# RV8trimRelays.net
KiCad netlist of a schematic drawn in EAGLE
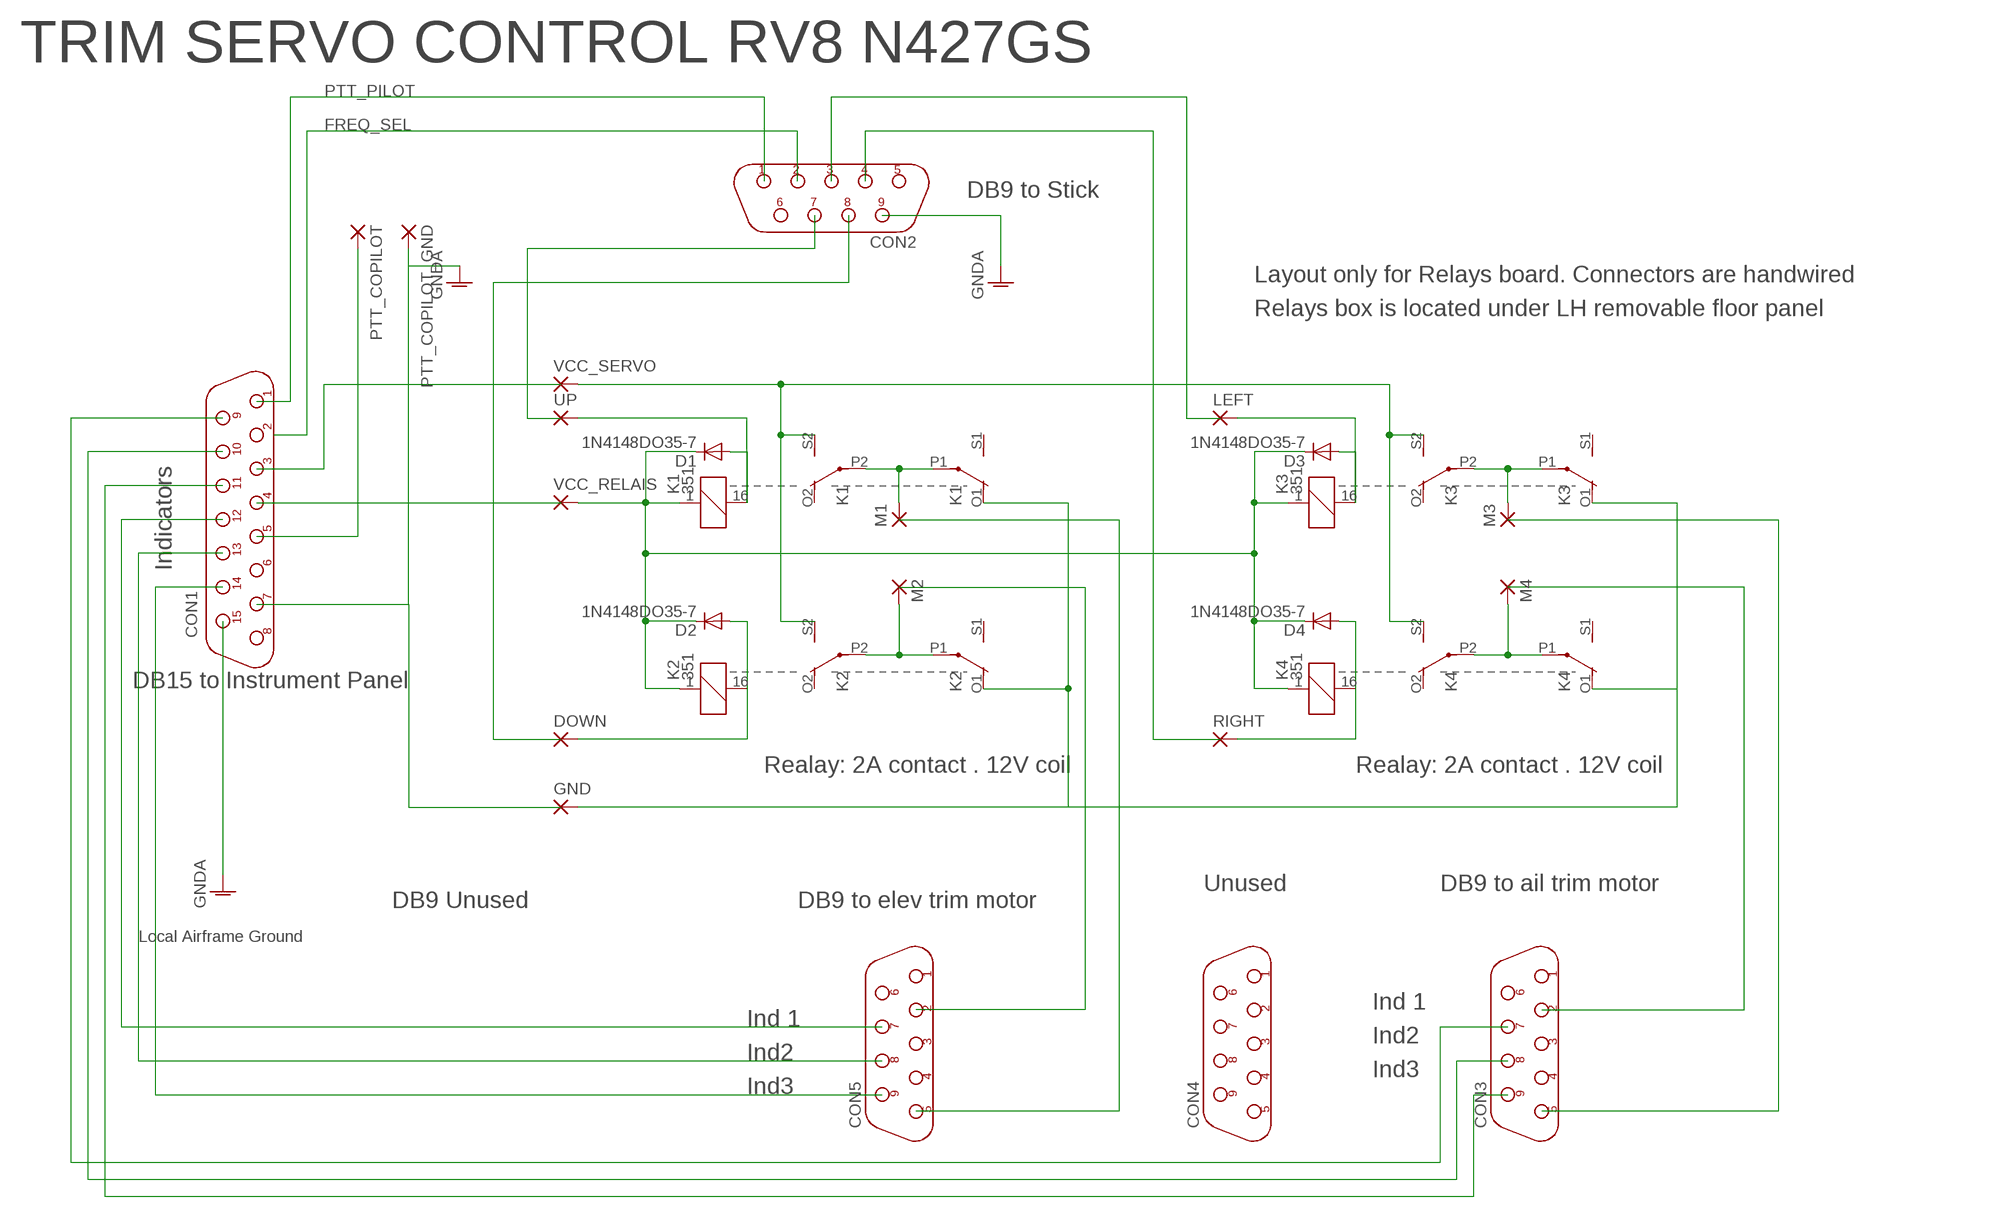
[diagram p0: schematic, sheet 1]

(export (version "E")
  (design (tool "Eeschema 10.0.6"))
  (components
    (comp (ref "CON1")
      (value "DB15F")
      (footprint "eagle-import:D-15F")
      (libsource (lib "eagle-import") (part "DB15F"))
    )
    (comp (ref "CON2")
      (value "DB9F")
      (footprint "eagle-import:D-09F")
      (libsource (lib "eagle-import") (part "DB9F"))
    )
    (comp (ref "CON3")
      (value "DB9F")
      (footprint "eagle-import:D-09F")
      (libsource (lib "eagle-import") (part "DB9F"))
    )
    (comp (ref "CON4")
      (value "DB9F")
      (footprint "eagle-import:D-09F")
      (libsource (lib "eagle-import") (part "DB9F"))
    )
    (comp (ref "CON5")
      (value "DB9F")
      (footprint "eagle-import:D-09F")
      (libsource (lib "eagle-import") (part "DB9F"))
    )
    (comp (ref "D1")
      (value "1N4148DO35-7")
      (footprint "eagle-import:DO35-7")
      (libsource (lib "eagle-import") (part "1N4148DO35-7"))
    )
    (comp (ref "D2")
      (value "1N4148DO35-7")
      (footprint "eagle-import:DO35-7")
      (libsource (lib "eagle-import") (part "1N4148DO35-7"))
    )
    (comp (ref "D3")
      (value "1N4148DO35-7")
      (footprint "eagle-import:DO35-7")
      (libsource (lib "eagle-import") (part "1N4148DO35-7"))
    )
    (comp (ref "D4")
      (value "1N4148DO35-7")
      (footprint "eagle-import:DO35-7")
      (libsource (lib "eagle-import") (part "1N4148DO35-7"))
    )
    (comp (ref "DOWN")
      (value "2,15/1,0")
      (footprint "eagle-import:2,15_1,0")
      (libsource (lib "eagle-import") (part "2,15/1,0"))
    )
    (comp (ref "GND")
      (value "2,15/1,0")
      (footprint "eagle-import:2,15_1,0")
      (libsource (lib "eagle-import") (part "2,15/1,0"))
    )
    (comp (ref "K1")
      (value "351")
      (footprint "eagle-import:351")
      (libsource (lib "eagle-import") (part "351"))
    )
    (comp (ref "K2")
      (value "351")
      (footprint "eagle-import:351")
      (libsource (lib "eagle-import") (part "351"))
    )
    (comp (ref "K3")
      (value "351")
      (footprint "eagle-import:351")
      (libsource (lib "eagle-import") (part "351"))
    )
    (comp (ref "K4")
      (value "351")
      (footprint "eagle-import:351")
      (libsource (lib "eagle-import") (part "351"))
    )
    (comp (ref "LEFT")
      (value "2,15/1,0")
      (footprint "eagle-import:2,15_1,0")
      (libsource (lib "eagle-import") (part "2,15/1,0"))
    )
    (comp (ref "M1")
      (value "2,15/1,0")
      (footprint "eagle-import:2,15_1,0")
      (libsource (lib "eagle-import") (part "2,15/1,0"))
    )
    (comp (ref "M2")
      (value "2,15/1,0")
      (footprint "eagle-import:2,15_1,0")
      (libsource (lib "eagle-import") (part "2,15/1,0"))
    )
    (comp (ref "M3")
      (value "2,15/1,0")
      (footprint "eagle-import:2,15_1,0")
      (libsource (lib "eagle-import") (part "2,15/1,0"))
    )
    (comp (ref "M4")
      (value "2,15/1,0")
      (footprint "eagle-import:2,15_1,0")
      (libsource (lib "eagle-import") (part "2,15/1,0"))
    )
    (comp (ref "PTT_COPILOT")
      (value "2,15/1,0")
      (footprint "eagle-import:2,15_1,0")
      (libsource (lib "eagle-import") (part "2,15/1,0"))
    )
    (comp (ref "PTT_COPILOT_GND")
      (value "2,15/1,0")
      (footprint "eagle-import:2,15_1,0")
      (libsource (lib "eagle-import") (part "2,15/1,0"))
    )
    (comp (ref "RIGHT")
      (value "2,15/1,0")
      (footprint "eagle-import:2,15_1,0")
      (libsource (lib "eagle-import") (part "2,15/1,0"))
    )
    (comp (ref "UP")
      (value "2,15/1,0")
      (footprint "eagle-import:2,15_1,0")
      (libsource (lib "eagle-import") (part "2,15/1,0"))
    )
    (comp (ref "VCC_RELAIS")
      (value "2,15/1,0")
      (footprint "eagle-import:2,15_1,0")
      (libsource (lib "eagle-import") (part "2,15/1,0"))
    )
    (comp (ref "VCC_SERVO")
      (value "2,15/1,0")
      (footprint "eagle-import:2,15_1,0")
      (libsource (lib "eagle-import") (part "2,15/1,0"))
    )
  )
  (nets
    (net (code "1") (name "/FREQ_SEL") (class "Default")
      (node (ref "CON2") (pin "2") (pinfunction "2_2") (pintype "passive"))
    )
    (net (code "2") (name "/PTT_PILOT") (class "Default")
      (node (ref "CON1") (pin "1") (pinfunction "1_1") (pintype "passive"))
      (node (ref "CON2") (pin "1") (pinfunction "1_1") (pintype "passive"))
    )
    (net (code "3") (name "GNDA") (class "Default")
      (node (ref "CON1") (pin "15") (pinfunction "15_15") (pintype "passive"))
      (node (ref "CON1") (pin "7") (pinfunction "7_7") (pintype "passive"))
      (node (ref "CON2") (pin "9") (pinfunction "9_9") (pintype "passive"))
      (node (ref "PTT_COPILOT_GND") (pin "1") (pinfunction "P_1") (pintype "passive"))
    )
    (net (code "4") (name "Net-(CON1-Pad9)") (class "Default")
      (node (ref "CON1") (pin "9") (pinfunction "9_9") (pintype "passive"))
      (node (ref "CON3") (pin "7") (pinfunction "7_7") (pintype "passive"))
    )
    (net (code "5") (name "Net-(CON1-Pad10)") (class "Default")
      (node (ref "CON1") (pin "10") (pinfunction "10_10") (pintype "passive"))
      (node (ref "CON3") (pin "8") (pinfunction "8_8") (pintype "passive"))
    )
    (net (code "6") (name "Net-(CON1-Pad11)") (class "Default")
      (node (ref "CON1") (pin "11") (pinfunction "11_11") (pintype "passive"))
      (node (ref "CON3") (pin "9") (pinfunction "9_9") (pintype "passive"))
    )
    (net (code "7") (name "Net-(CON1-Pad12)") (class "Default")
      (node (ref "CON1") (pin "12") (pinfunction "12_12") (pintype "passive"))
      (node (ref "CON5") (pin "7") (pinfunction "7_7") (pintype "passive"))
    )
    (net (code "8") (name "Net-(CON1-Pad13)") (class "Default")
      (node (ref "CON1") (pin "13") (pinfunction "13_13") (pintype "passive"))
      (node (ref "CON5") (pin "8") (pinfunction "8_8") (pintype "passive"))
    )
    (net (code "9") (name "Net-(CON1-Pad14)") (class "Default")
      (node (ref "CON1") (pin "14") (pinfunction "14_14") (pintype "passive"))
      (node (ref "CON5") (pin "9") (pinfunction "9_9") (pintype "passive"))
    )
    (net (code "10") (name "Net-(DOWN-P)") (class "Default")
      (node (ref "D2") (pin "A") (pinfunction "A_A") (pintype "passive"))
      (node (ref "DOWN") (pin "1") (pinfunction "P_1") (pintype "passive"))
      (node (ref "K2") (pin "16") (pinfunction "2_16") (pintype "passive"))
    )
    (net (code "11") (name "Net-(GND-P)") (class "Default")
      (node (ref "GND") (pin "1") (pinfunction "P_1") (pintype "passive"))
      (node (ref "K1") (pin "O1") (pinfunction "O_O1") (pintype "passive"))
      (node (ref "K2") (pin "O1") (pinfunction "O_O1") (pintype "passive"))
      (node (ref "K3") (pin "O1") (pinfunction "O_O1") (pintype "passive"))
      (node (ref "K4") (pin "O1") (pinfunction "O_O1") (pintype "passive"))
    )
    (net (code "12") (name "Net-(K1A-2)") (class "Default")
      (node (ref "D1") (pin "A") (pinfunction "A_A") (pintype "passive"))
      (node (ref "K1") (pin "16") (pinfunction "2_16") (pintype "passive"))
      (node (ref "UP") (pin "1") (pinfunction "P_1") (pintype "passive"))
    )
    (net (code "13") (name "Net-(K1B-P)") (class "Default")
      (node (ref "K1") (pin "P1") (pinfunction "P_P1") (pintype "passive"))
      (node (ref "K1") (pin "P2") (pinfunction "P_P2") (pintype "passive"))
      (node (ref "M1") (pin "1") (pinfunction "P_1") (pintype "passive"))
    )
    (net (code "14") (name "Net-(K1C-S)") (class "Default")
      (node (ref "K1") (pin "S2") (pinfunction "S_S2") (pintype "passive"))
      (node (ref "K2") (pin "S2") (pinfunction "S_S2") (pintype "passive"))
      (node (ref "K3") (pin "S2") (pinfunction "S_S2") (pintype "passive"))
      (node (ref "K4") (pin "S2") (pinfunction "S_S2") (pintype "passive"))
      (node (ref "VCC_SERVO") (pin "1") (pinfunction "P_1") (pintype "passive"))
    )
    (net (code "15") (name "Net-(K2B-P)") (class "Default")
      (node (ref "K2") (pin "P1") (pinfunction "P_P1") (pintype "passive"))
      (node (ref "K2") (pin "P2") (pinfunction "P_P2") (pintype "passive"))
      (node (ref "M2") (pin "1") (pinfunction "P_1") (pintype "passive"))
    )
    (net (code "16") (name "Net-(K3A-2)") (class "Default")
      (node (ref "D3") (pin "A") (pinfunction "A_A") (pintype "passive"))
      (node (ref "K3") (pin "16") (pinfunction "2_16") (pintype "passive"))
      (node (ref "LEFT") (pin "1") (pinfunction "P_1") (pintype "passive"))
    )
    (net (code "17") (name "Net-(K3B-P)") (class "Default")
      (node (ref "K3") (pin "P1") (pinfunction "P_P1") (pintype "passive"))
      (node (ref "K3") (pin "P2") (pinfunction "P_P2") (pintype "passive"))
      (node (ref "M3") (pin "1") (pinfunction "P_1") (pintype "passive"))
    )
    (net (code "18") (name "Net-(K4A-2)") (class "Default")
      (node (ref "D4") (pin "A") (pinfunction "A_A") (pintype "passive"))
      (node (ref "K4") (pin "16") (pinfunction "2_16") (pintype "passive"))
      (node (ref "RIGHT") (pin "1") (pinfunction "P_1") (pintype "passive"))
    )
    (net (code "19") (name "Net-(K4B-P)") (class "Default")
      (node (ref "K4") (pin "P1") (pinfunction "P_P1") (pintype "passive"))
      (node (ref "K4") (pin "P2") (pinfunction "P_P2") (pintype "passive"))
      (node (ref "M4") (pin "1") (pinfunction "P_1") (pintype "passive"))
    )
    (net (code "20") (name "Net-(PTT_COPILOT-P)") (class "Default")
      (node (ref "CON1") (pin "5") (pinfunction "5_5") (pintype "passive"))
      (node (ref "PTT_COPILOT") (pin "1") (pinfunction "P_1") (pintype "passive"))
    )
    (net (code "21") (name "Net-(VCC_RELAIS-P)") (class "Default")
      (node (ref "D1") (pin "C") (pinfunction "C_C") (pintype "passive"))
      (node (ref "D2") (pin "C") (pinfunction "C_C") (pintype "passive"))
      (node (ref "D3") (pin "C") (pinfunction "C_C") (pintype "passive"))
      (node (ref "D4") (pin "C") (pinfunction "C_C") (pintype "passive"))
      (node (ref "K1") (pin "1") (pinfunction "1_1") (pintype "passive"))
      (node (ref "K2") (pin "1") (pinfunction "1_1") (pintype "passive"))
      (node (ref "K3") (pin "1") (pinfunction "1_1") (pintype "passive"))
      (node (ref "K4") (pin "1") (pinfunction "1_1") (pintype "passive"))
      (node (ref "VCC_RELAIS") (pin "1") (pinfunction "P_1") (pintype "passive"))
    )
    (net (code "22") (name "unconnected-(CON1-Pad2)") (class "Default")
      (node (ref "CON1") (pin "2") (pinfunction "2_2") (pintype "passive"))
    )
    (net (code "23") (name "unconnected-(CON1-Pad3)") (class "Default")
      (node (ref "CON1") (pin "3") (pinfunction "3_3") (pintype "passive"))
    )
    (net (code "24") (name "unconnected-(CON1-Pad4)") (class "Default")
      (node (ref "CON1") (pin "4") (pinfunction "4_4") (pintype "passive"))
    )
    (net (code "25") (name "unconnected-(CON1-Pad6)") (class "Default")
      (node (ref "CON1") (pin "6") (pinfunction "6_6") (pintype "passive"))
    )
    (net (code "26") (name "unconnected-(CON1-Pad8)") (class "Default")
      (node (ref "CON1") (pin "8") (pinfunction "8_8") (pintype "passive"))
    )
    (net (code "27") (name "unconnected-(CON2-Pad3)") (class "Default")
      (node (ref "CON2") (pin "3") (pinfunction "3_3") (pintype "passive"))
    )
    (net (code "28") (name "unconnected-(CON2-Pad4)") (class "Default")
      (node (ref "CON2") (pin "4") (pinfunction "4_4") (pintype "passive"))
    )
    (net (code "29") (name "unconnected-(CON2-Pad5)") (class "Default")
      (node (ref "CON2") (pin "5") (pinfunction "5_5") (pintype "passive"))
    )
    (net (code "30") (name "unconnected-(CON2-Pad6)") (class "Default")
      (node (ref "CON2") (pin "6") (pinfunction "6_6") (pintype "passive"))
    )
    (net (code "31") (name "unconnected-(CON2-Pad7)") (class "Default")
      (node (ref "CON2") (pin "7") (pinfunction "7_7") (pintype "passive"))
    )
    (net (code "32") (name "unconnected-(CON2-Pad8)") (class "Default")
      (node (ref "CON2") (pin "8") (pinfunction "8_8") (pintype "passive"))
    )
    (net (code "33") (name "unconnected-(CON3-Pad1)") (class "Default")
      (node (ref "CON3") (pin "1") (pinfunction "1_1") (pintype "passive"))
    )
    (net (code "34") (name "unconnected-(CON3-Pad2)") (class "Default")
      (node (ref "CON3") (pin "2") (pinfunction "2_2") (pintype "passive"))
    )
    (net (code "35") (name "unconnected-(CON3-Pad3)") (class "Default")
      (node (ref "CON3") (pin "3") (pinfunction "3_3") (pintype "passive"))
    )
    (net (code "36") (name "unconnected-(CON3-Pad4)") (class "Default")
      (node (ref "CON3") (pin "4") (pinfunction "4_4") (pintype "passive"))
    )
    (net (code "37") (name "unconnected-(CON3-Pad5)") (class "Default")
      (node (ref "CON3") (pin "5") (pinfunction "5_5") (pintype "passive"))
    )
    (net (code "38") (name "unconnected-(CON3-Pad6)") (class "Default")
      (node (ref "CON3") (pin "6") (pinfunction "6_6") (pintype "passive"))
    )
    (net (code "39") (name "unconnected-(CON4-Pad1)") (class "Default")
      (node (ref "CON4") (pin "1") (pinfunction "1_1") (pintype "passive"))
    )
    (net (code "40") (name "unconnected-(CON4-Pad2)") (class "Default")
      (node (ref "CON4") (pin "2") (pinfunction "2_2") (pintype "passive"))
    )
    (net (code "41") (name "unconnected-(CON4-Pad3)") (class "Default")
      (node (ref "CON4") (pin "3") (pinfunction "3_3") (pintype "passive"))
    )
    (net (code "42") (name "unconnected-(CON4-Pad4)") (class "Default")
      (node (ref "CON4") (pin "4") (pinfunction "4_4") (pintype "passive"))
    )
    (net (code "43") (name "unconnected-(CON4-Pad5)") (class "Default")
      (node (ref "CON4") (pin "5") (pinfunction "5_5") (pintype "passive"))
    )
    (net (code "44") (name "unconnected-(CON4-Pad6)") (class "Default")
      (node (ref "CON4") (pin "6") (pinfunction "6_6") (pintype "passive"))
    )
    (net (code "45") (name "unconnected-(CON4-Pad7)") (class "Default")
      (node (ref "CON4") (pin "7") (pinfunction "7_7") (pintype "passive"))
    )
    (net (code "46") (name "unconnected-(CON4-Pad8)") (class "Default")
      (node (ref "CON4") (pin "8") (pinfunction "8_8") (pintype "passive"))
    )
    (net (code "47") (name "unconnected-(CON4-Pad9)") (class "Default")
      (node (ref "CON4") (pin "9") (pinfunction "9_9") (pintype "passive"))
    )
    (net (code "48") (name "unconnected-(CON5-Pad1)") (class "Default")
      (node (ref "CON5") (pin "1") (pinfunction "1_1") (pintype "passive"))
    )
    (net (code "49") (name "unconnected-(CON5-Pad2)") (class "Default")
      (node (ref "CON5") (pin "2") (pinfunction "2_2") (pintype "passive"))
    )
    (net (code "50") (name "unconnected-(CON5-Pad3)") (class "Default")
      (node (ref "CON5") (pin "3") (pinfunction "3_3") (pintype "passive"))
    )
    (net (code "51") (name "unconnected-(CON5-Pad4)") (class "Default")
      (node (ref "CON5") (pin "4") (pinfunction "4_4") (pintype "passive"))
    )
    (net (code "52") (name "unconnected-(CON5-Pad5)") (class "Default")
      (node (ref "CON5") (pin "5") (pinfunction "5_5") (pintype "passive"))
    )
    (net (code "53") (name "unconnected-(CON5-Pad6)") (class "Default")
      (node (ref "CON5") (pin "6") (pinfunction "6_6") (pintype "passive"))
    )
    (net (code "54") (name "unconnected-(K1B-S-PadS1)") (class "Default")
      (node (ref "K1") (pin "S1") (pinfunction "S_S1") (pintype "passive"))
    )
    (net (code "55") (name "unconnected-(K1C-O-PadO2)") (class "Default")
      (node (ref "K1") (pin "O2") (pinfunction "O_O2") (pintype "passive"))
    )
    (net (code "56") (name "unconnected-(K2B-S-PadS1)") (class "Default")
      (node (ref "K2") (pin "S1") (pinfunction "S_S1") (pintype "passive"))
    )
    (net (code "57") (name "unconnected-(K2C-O-PadO2)") (class "Default")
      (node (ref "K2") (pin "O2") (pinfunction "O_O2") (pintype "passive"))
    )
    (net (code "58") (name "unconnected-(K3B-S-PadS1)") (class "Default")
      (node (ref "K3") (pin "S1") (pinfunction "S_S1") (pintype "passive"))
    )
    (net (code "59") (name "unconnected-(K3C-O-PadO2)") (class "Default")
      (node (ref "K3") (pin "O2") (pinfunction "O_O2") (pintype "passive"))
    )
    (net (code "60") (name "unconnected-(K4B-S-PadS1)") (class "Default")
      (node (ref "K4") (pin "S1") (pinfunction "S_S1") (pintype "passive"))
    )
    (net (code "61") (name "unconnected-(K4C-O-PadO2)") (class "Default")
      (node (ref "K4") (pin "O2") (pinfunction "O_O2") (pintype "passive"))
    )
  )
)
